# dumper.net
KiCad netlist of a schematic drawn in EAGLE
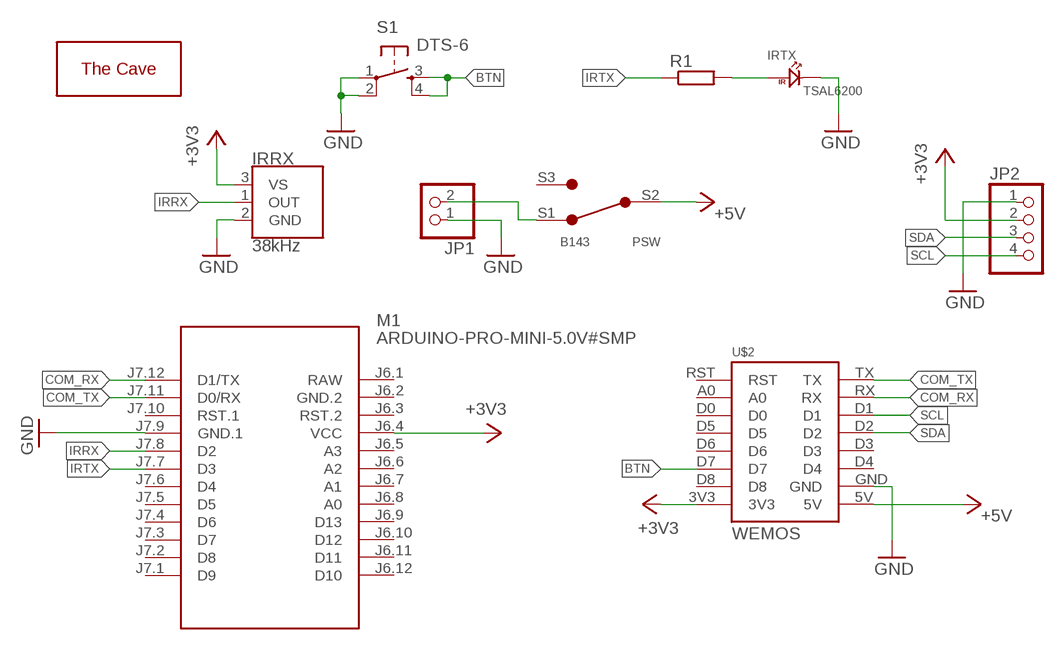
[diagram p0: schematic, sheet 1]

(export (version "E")
  (design (tool "Eeschema 10.0.6"))
  (components
    (comp (ref "IRRX")
      (value "38kHz")
      (footprint "eagle-import:TSOP382")
      (libsource (lib "eagle-import") (part "TSOP38238"))
    )
    (comp (ref "IRTX")
      (value "TSAL6200")
      (footprint "eagle-import:TSAL6200")
      (libsource (lib "eagle-import") (part "TSAL6200"))
    )
    (comp (ref "JP1")
      (value "PINHD-1X2")
      (footprint "eagle-import:1X02")
      (libsource (lib "eagle-import") (part "PINHD-1X2"))
    )
    (comp (ref "JP2")
      (value "PINHD-1X4")
      (footprint "eagle-import:1X04")
      (libsource (lib "eagle-import") (part "PINHD-1X4"))
    )
    (comp (ref "M1")
      (value "ARDUINO-PRO-MINI-5.0V#SMP")
      (footprint "eagle-import:ARDUINO-PRO-MINI#SMP")
      (libsource (lib "eagle-import") (part "ARDUINO-PRO-MINI-#SMP5.0V"))
    )
    (comp (ref "PSW")
      (value "B143")
      (footprint "eagle-import:B143")
      (libsource (lib "eagle-import") (part "B143"))
    )
    (comp (ref "R1")
      (value "R-EU_0207/7")
      (footprint "eagle-import:0207_7")
      (libsource (lib "eagle-import") (part "R-EU_0207/7"))
    )
    (comp (ref "S1")
      (value "DTS-6")
      (footprint "eagle-import:DTS-6")
      (libsource (lib "eagle-import") (part "DTS-6"))
    )
    (comp (ref "U$1")
      (value "THECAVE_LOGO_NEW_TOP_SMALL")
      (footprint "eagle-import:NEW_LOGO_SMALL_TOP")
      (libsource (lib "eagle-import") (part "THECAVE_LOGO_NEW_TOP_SMALL"))
    )
    (comp (ref "U$2")
      (value "WEMOS")
      (footprint "eagle-import:WEMOS")
      (libsource (lib "eagle-import") (part "WEMOS"))
    )
  )
  (nets
    (net (code "1") (name "+3V3") (class "Default")
      (node (ref "IRRX") (pin "3") (pinfunction "VS_3") (pintype "bidirectional"))
      (node (ref "JP2") (pin "2") (pinfunction "2_2") (pintype "passive"))
      (node (ref "M1") (pin "J6.4") (pinfunction "VCC_J6.4") (pintype "power_in"))
      (node (ref "U$2") (pin "3V3") (pinfunction "3V3_3V3") (pintype "bidirectional"))
    )
    (net (code "2") (name "+5V") (class "Default")
      (node (ref "PSW") (pin "S2") (pinfunction "COM_S2") (pintype "bidirectional"))
      (node (ref "U$2") (pin "5V") (pinfunction "5V_5V") (pintype "bidirectional"))
    )
    (net (code "3") (name "/GND.2") (class "Default")
      (node (ref "M1") (pin "J6.2") (pinfunction "GND.2_J6.2") (pintype "power_in"))
    )
    (net (code "4") (name "/RAW") (class "Default")
      (node (ref "M1") (pin "J6.1") (pinfunction "RAW_J6.1") (pintype "power_in"))
    )
    (net (code "5") (name "BTN") (class "Default")
      (node (ref "S1") (pin "3") (pinfunction "3_3") (pintype "passive"))
      (node (ref "S1") (pin "4") (pinfunction "4_4") (pintype "passive"))
      (node (ref "U$2") (pin "D7") (pinfunction "D7_D7") (pintype "bidirectional"))
    )
    (net (code "6") (name "COM_RX") (class "Default")
      (node (ref "M1") (pin "J7.12") (pinfunction "D1/TX_J7.12") (pintype "bidirectional"))
      (node (ref "U$2") (pin "RX") (pinfunction "RX_RX") (pintype "bidirectional"))
    )
    (net (code "7") (name "COM_TX") (class "Default")
      (node (ref "M1") (pin "J7.11") (pinfunction "D0/RX_J7.11") (pintype "bidirectional"))
      (node (ref "U$2") (pin "TX") (pinfunction "TX_TX") (pintype "bidirectional"))
    )
    (net (code "8") (name "GND") (class "Default")
      (node (ref "IRRX") (pin "2") (pinfunction "GND_2") (pintype "bidirectional"))
      (node (ref "IRTX") (pin "N") (pinfunction "N_N") (pintype "bidirectional"))
      (node (ref "JP1") (pin "1") (pinfunction "1_1") (pintype "passive"))
      (node (ref "JP2") (pin "1") (pinfunction "1_1") (pintype "passive"))
      (node (ref "M1") (pin "J7.9") (pinfunction "GND.1_J7.9") (pintype "power_in"))
      (node (ref "S1") (pin "1") (pinfunction "1_1") (pintype "passive"))
      (node (ref "S1") (pin "2") (pinfunction "2_2") (pintype "passive"))
      (node (ref "U$2") (pin "GND") (pinfunction "GND_GND") (pintype "bidirectional"))
    )
    (net (code "9") (name "IRRX") (class "Default")
      (node (ref "IRRX") (pin "1") (pinfunction "OUT_1") (pintype "bidirectional"))
      (node (ref "M1") (pin "J7.8") (pinfunction "D2_J7.8") (pintype "bidirectional"))
    )
    (net (code "10") (name "IRTX") (class "Default")
      (node (ref "M1") (pin "J7.7") (pinfunction "D3_J7.7") (pintype "bidirectional"))
      (node (ref "R1") (pin "1") (pinfunction "1_1") (pintype "passive"))
    )
    (net (code "11") (name "Net-(IRTX-PadP)") (class "Default")
      (node (ref "IRTX") (pin "P") (pinfunction "P_P") (pintype "bidirectional"))
      (node (ref "R1") (pin "2") (pinfunction "2_2") (pintype "passive"))
    )
    (net (code "12") (name "Net-(JP1-Pad2)") (class "Default")
      (node (ref "JP1") (pin "2") (pinfunction "2_2") (pintype "passive"))
      (node (ref "PSW") (pin "S1") (pinfunction "S1_S1") (pintype "bidirectional"))
    )
    (net (code "13") (name "SCL") (class "Default")
      (node (ref "JP2") (pin "4") (pinfunction "4_4") (pintype "passive"))
      (node (ref "U$2") (pin "D1") (pinfunction "D1_D1") (pintype "bidirectional"))
    )
    (net (code "14") (name "SDA") (class "Default")
      (node (ref "JP2") (pin "3") (pinfunction "3_3") (pintype "passive"))
      (node (ref "U$2") (pin "D2") (pinfunction "D2_D2") (pintype "bidirectional"))
    )
    (net (code "15") (name "unconnected-(M1-A0-PadJ6.8)") (class "Default")
      (node (ref "M1") (pin "J6.8") (pinfunction "A0_J6.8") (pintype "bidirectional"))
    )
    (net (code "16") (name "unconnected-(M1-A1-PadJ6.7)") (class "Default")
      (node (ref "M1") (pin "J6.7") (pinfunction "A1_J6.7") (pintype "bidirectional"))
    )
    (net (code "17") (name "unconnected-(M1-A2-PadJ6.6)") (class "Default")
      (node (ref "M1") (pin "J6.6") (pinfunction "A2_J6.6") (pintype "bidirectional"))
    )
    (net (code "18") (name "unconnected-(M1-A3-PadJ6.5)") (class "Default")
      (node (ref "M1") (pin "J6.5") (pinfunction "A3_J6.5") (pintype "bidirectional"))
    )
    (net (code "19") (name "unconnected-(M1-D4-PadJ7.6)") (class "Default")
      (node (ref "M1") (pin "J7.6") (pinfunction "D4_J7.6") (pintype "bidirectional"))
    )
    (net (code "20") (name "unconnected-(M1-D5-PadJ7.5)") (class "Default")
      (node (ref "M1") (pin "J7.5") (pinfunction "D5_J7.5") (pintype "bidirectional"))
    )
    (net (code "21") (name "unconnected-(M1-D6-PadJ7.4)") (class "Default")
      (node (ref "M1") (pin "J7.4") (pinfunction "D6_J7.4") (pintype "bidirectional"))
    )
    (net (code "22") (name "unconnected-(M1-D7-PadJ7.3)") (class "Default")
      (node (ref "M1") (pin "J7.3") (pinfunction "D7_J7.3") (pintype "bidirectional"))
    )
    (net (code "23") (name "unconnected-(M1-D8-PadJ7.2)") (class "Default")
      (node (ref "M1") (pin "J7.2") (pinfunction "D8_J7.2") (pintype "bidirectional"))
    )
    (net (code "24") (name "unconnected-(M1-D9-PadJ7.1)") (class "Default")
      (node (ref "M1") (pin "J7.1") (pinfunction "D9_J7.1") (pintype "bidirectional"))
    )
    (net (code "25") (name "unconnected-(M1-D10-PadJ6.12)") (class "Default")
      (node (ref "M1") (pin "J6.12") (pinfunction "D10_J6.12") (pintype "bidirectional"))
    )
    (net (code "26") (name "unconnected-(M1-D11-PadJ6.11)") (class "Default")
      (node (ref "M1") (pin "J6.11") (pinfunction "D11_J6.11") (pintype "bidirectional"))
    )
    (net (code "27") (name "unconnected-(M1-D12-PadJ6.10)") (class "Default")
      (node (ref "M1") (pin "J6.10") (pinfunction "D12_J6.10") (pintype "bidirectional"))
    )
    (net (code "28") (name "unconnected-(M1-D13-PadJ6.9)") (class "Default")
      (node (ref "M1") (pin "J6.9") (pinfunction "D13_J6.9") (pintype "bidirectional"))
    )
    (net (code "29") (name "unconnected-(M1-RST.1-PadJ7.10)") (class "Default")
      (node (ref "M1") (pin "J7.10") (pinfunction "RST.1_J7.10") (pintype "bidirectional"))
    )
    (net (code "30") (name "unconnected-(M1-RST.2-PadJ6.3)") (class "Default")
      (node (ref "M1") (pin "J6.3") (pinfunction "RST.2_J6.3") (pintype "bidirectional"))
    )
    (net (code "31") (name "unconnected-(PSW-S2-PadS3)") (class "Default")
      (node (ref "PSW") (pin "S3") (pinfunction "S2_S3") (pintype "bidirectional"))
    )
    (net (code "32") (name "unconnected-(U$2-PadA0)") (class "Default")
      (node (ref "U$2") (pin "A0") (pinfunction "A0_A0") (pintype "bidirectional"))
    )
    (net (code "33") (name "unconnected-(U$2-PadD0)") (class "Default")
      (node (ref "U$2") (pin "D0") (pinfunction "D0_D0") (pintype "bidirectional"))
    )
    (net (code "34") (name "unconnected-(U$2-PadD3)") (class "Default")
      (node (ref "U$2") (pin "D3") (pinfunction "D3_D3") (pintype "bidirectional"))
    )
    (net (code "35") (name "unconnected-(U$2-PadD4)") (class "Default")
      (node (ref "U$2") (pin "D4") (pinfunction "D4_D4") (pintype "bidirectional"))
    )
    (net (code "36") (name "unconnected-(U$2-PadD5)") (class "Default")
      (node (ref "U$2") (pin "D5") (pinfunction "D5_D5") (pintype "bidirectional"))
    )
    (net (code "37") (name "unconnected-(U$2-PadD6)") (class "Default")
      (node (ref "U$2") (pin "D6") (pinfunction "D6_D6") (pintype "bidirectional"))
    )
    (net (code "38") (name "unconnected-(U$2-PadD8)") (class "Default")
      (node (ref "U$2") (pin "D8") (pinfunction "D8_D8") (pintype "bidirectional"))
    )
    (net (code "39") (name "unconnected-(U$2-PadRST)") (class "Default")
      (node (ref "U$2") (pin "RST") (pinfunction "RST_RST") (pintype "bidirectional"))
    )
  )
)
